# BLDC.net
KiCad netlist of a schematic drawn in Altium Designer
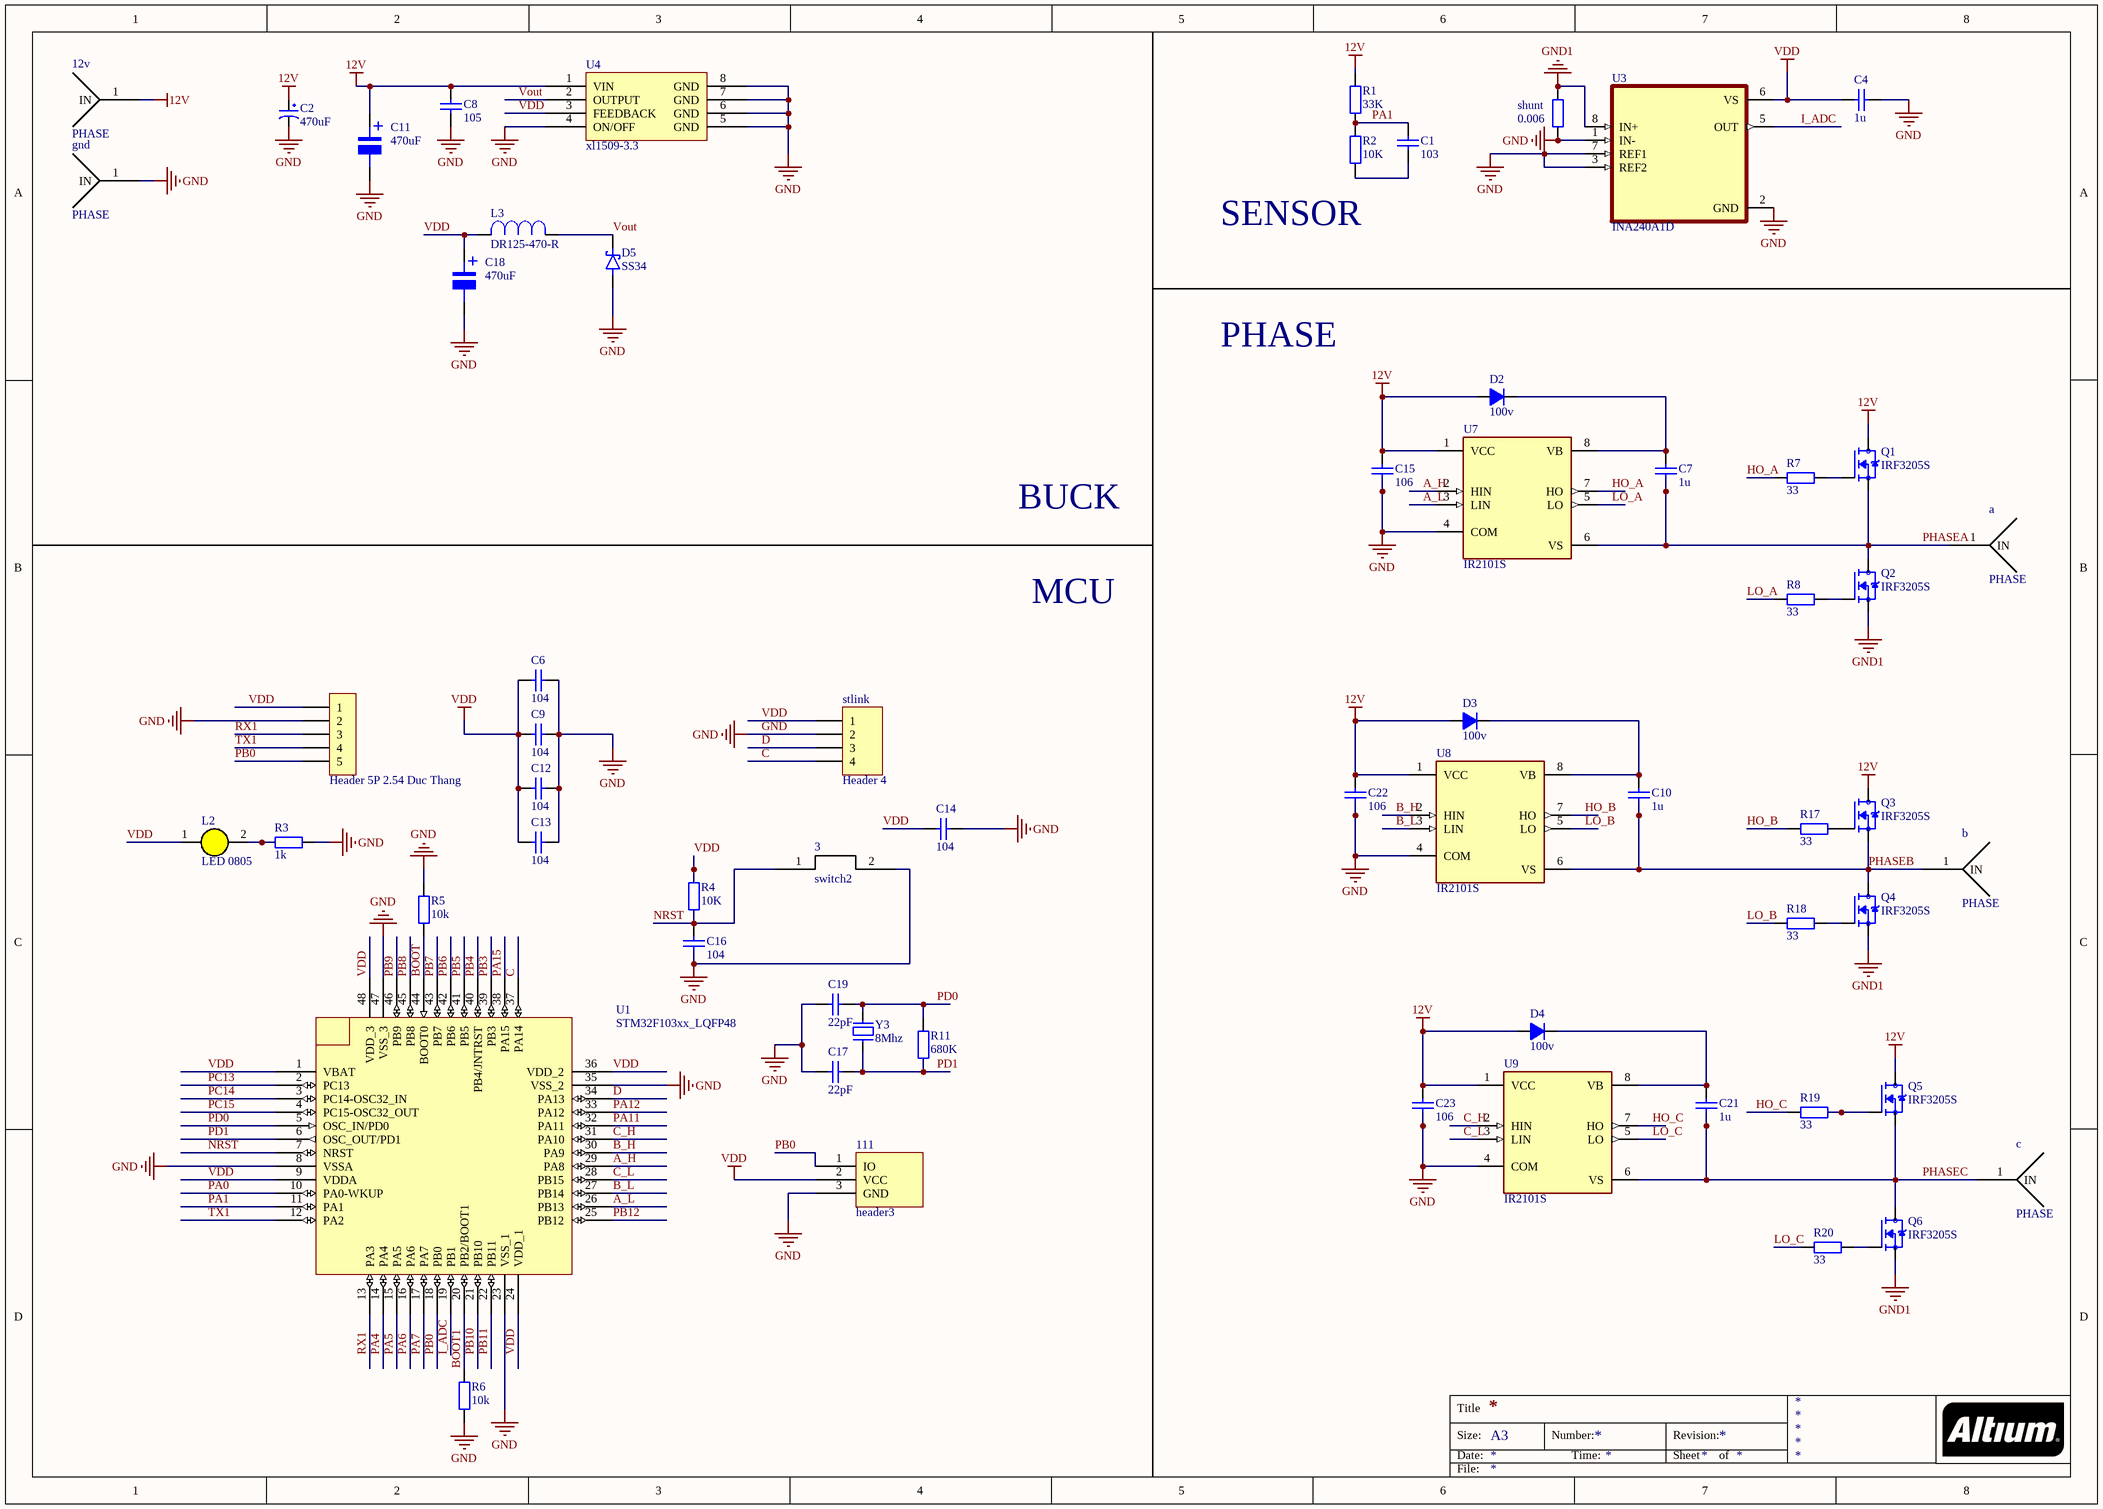
[diagram p0: BLDC.SchDoc]

(export (version "E")
  (design (tool "Eeschema 10.0.6"))
  (components
    (comp (ref "3") (value "switch2") (footprint "switch") (libsource (lib "TV1") (part "switch2")))
    (comp (ref "12v")
      (value "PHASE")
      (footprint "PCBComponent_1 - duplicate")
      (libsource (lib "TV1") (part "PHASE"))
    )
    (comp (ref "111") (value "header3") (footprint "Edge Connector") (libsource (lib "TV") (part "header3")))
    (comp (ref "a")
      (value "PHASE")
      (footprint "PCBComponent_1 - duplicate")
      (libsource (lib "TV1") (part "PHASE"))
    )
    (comp (ref "b")
      (value "PHASE")
      (footprint "PCBComponent_1 - duplicate")
      (libsource (lib "TV1") (part "PHASE"))
    )
    (comp (ref "c")
      (value "PHASE")
      (footprint "PCBComponent_1 - duplicate")
      (libsource (lib "TV1") (part "PHASE"))
    )
    (comp (ref "C1")
      (value "103")
      (footprint "tu 0805")
      (description "Dán")
      (libsource (lib "Altium_Lib_by_KhueNguyenCreator") (part "Tu 0805 22nF 50V 20%"))
    )
    (comp (ref "C2")
      (value "470uF")
      (footprint "TV1:TU HOA 10mm")
      (description "Cắm")
      (libsource (lib "TV1") (part "Tu Hoa 470uF 6.3V 8x11"))
    )
    (comp (ref "C4")
      (value "1u")
      (footprint "tu 0805")
      (description "Dán")
      (libsource (lib "Altium_Lib_by_KhueNguyenCreator") (part "Tu 0805 106 16V 10%"))
    )
    (comp (ref "C6")
      (value "104")
      (footprint "tu 0805")
      (description "Dán")
      (libsource (lib "Altium_Lib_by_KhueNguyenCreator") (part "Tu 0805 106 16V 10%"))
    )
    (comp (ref "C7")
      (value "1u")
      (footprint "tu 0805")
      (description "Dán")
      (libsource (lib "Altium_Lib_by_KhueNguyenCreator") (part "Tu 0805 10pF 50V 10%"))
    )
    (comp (ref "C8")
      (value "105")
      (footprint "tu 0805")
      (description "Dán")
      (libsource (lib "Altium_Lib_by_KhueNguyenCreator") (part "Tu 0805 105 50V 10%"))
    )
    (comp (ref "C9")
      (value "104")
      (footprint "tu 0805")
      (description "Dán")
      (libsource (lib "Altium_Lib_by_KhueNguyenCreator") (part "Tu 0805 106 16V 10%"))
    )
    (comp (ref "C10")
      (value "1u")
      (footprint "tu 0805")
      (description "Dán")
      (libsource (lib "Altium_Lib_by_KhueNguyenCreator") (part "Tu 0805 10pF 50V 10%"))
    )
    (comp (ref "C11")
      (value "470uF")
      (footprint "tu nhom 8 (f)")
      (description "Dán")
      (libsource (lib "Altium_Lib_by_KhueNguyenCreator") (part "Tu Nhom 470uF 16V"))
    )
    (comp (ref "C12")
      (value "104")
      (footprint "tu 0805")
      (description "Dán")
      (libsource (lib "Altium_Lib_by_KhueNguyenCreator") (part "Tu 0805 106 16V 10%"))
    )
    (comp (ref "C13")
      (value "104")
      (footprint "tu 0805")
      (description "Dán")
      (libsource (lib "Altium_Lib_by_KhueNguyenCreator") (part "Tu 0805 106 16V 10%"))
    )
    (comp (ref "C14")
      (value "104")
      (footprint "tu 0805")
      (description "Dán")
      (libsource (lib "Altium_Lib_by_KhueNguyenCreator") (part "Tu 0805 106 16V 10%"))
    )
    (comp (ref "C15")
      (value "106")
      (footprint "tu 0805")
      (description "Dán")
      (libsource (lib "Altium_Lib_by_KhueNguyenCreator") (part "Tu 0805 106 16V 10%"))
    )
    (comp (ref "C16")
      (value "104")
      (footprint "tu 0805")
      (description "Dán")
      (libsource (lib "Altium_Lib_by_KhueNguyenCreator") (part "Tu 0805 106 16V 10%"))
    )
    (comp (ref "C17")
      (value "22pF")
      (footprint "tu 0805")
      (description "Dán")
      (libsource (lib "Altium_Lib_by_KhueNguyenCreator") (part "Tu 0805 106 16V 10%"))
    )
    (comp (ref "C18")
      (value "470uF")
      (footprint "tu nhom 8 (f)")
      (description "Dán")
      (libsource (lib "Altium_Lib_by_KhueNguyenCreator") (part "Tu Nhom 470uF 16V"))
    )
    (comp (ref "C19")
      (value "22pF")
      (footprint "tu 0805")
      (description "Dán")
      (libsource (lib "Altium_Lib_by_KhueNguyenCreator") (part "Tu 0805 22pF 50V 10%"))
    )
    (comp (ref "C21")
      (value "1u")
      (footprint "tu 0805")
      (description "Dán")
      (libsource (lib "Altium_Lib_by_KhueNguyenCreator") (part "Tu 0805 10pF 50V 10%"))
    )
    (comp (ref "C22")
      (value "106")
      (footprint "tu 0805")
      (description "Dán")
      (libsource (lib "Altium_Lib_by_KhueNguyenCreator") (part "Tu 0805 106 16V 10%"))
    )
    (comp (ref "C23")
      (value "106")
      (footprint "tu 0805")
      (description "Dán")
      (libsource (lib "Altium_Lib_by_KhueNguyenCreator") (part "Tu 0805 106 16V 10%"))
    )
    (comp (ref "D2")
      (value "100v")
      (footprint "DIODE 0.5A")
      (description "Cắm")
      (libsource (lib "Altium_Lib_by_KhueNguyenCreator") (part "Diode 1N4148"))
    )
    (comp (ref "D3")
      (value "100v")
      (footprint "DIODE 0.5A")
      (description "Cắm")
      (libsource (lib "Altium_Lib_by_KhueNguyenCreator") (part "Diode 1N4148"))
    )
    (comp (ref "D4")
      (value "100v")
      (footprint "DIODE 0.5A")
      (description "Cắm")
      (libsource (lib "Altium_Lib_by_KhueNguyenCreator") (part "Diode 1N4148"))
    )
    (comp (ref "D5")
      (value "SS34")
      (footprint "DIOM794X590X250")
      (description "Diode Schottky 20V 3A 2Pin SMC ¦ Diodes Inc B320-13-F")
      (fields (field (name "MF") "Diodes Inc.") (field (name "MP") "B320-13-F"))
      (libsource (lib "NgTuanALib") (part "B320-13-F"))
    )
    (comp (ref "gnd")
      (value "PHASE")
      (footprint "PCBComponent_1 - duplicate")
      (libsource (lib "TV1") (part "PHASE"))
    )
    (comp (ref "H1")
      (value "Header 5P 2.54 Duc Thang")
      (footprint "XH2.54M-5")
      (description "Cắm")
      (libsource (lib "Altium_Lib_by_KhueNguyenCreator") (part "Header 5P 2.54 Duc Thang"))
    )
    (comp (ref "L2")
      (value "LED 0805")
      (footprint "LED-0805-Yellow")
      (description "Dán")
      (libsource (lib "Altium_Lib_by_KhueNguyenCreator") (part "LED 0805 Vang"))
    )
    (comp (ref "L3")
      (value "DR125-470-R")
      (footprint "INDM125125X600N")
      (fields (field (name "MF") "Eaton"))
      (libsource (lib "TV1") (part "DR125-470-R"))
    )
    (comp (ref "Q1")
      (value "IRF3205S")
      (footprint "TRANS_IRF3205S")
      (description "N-Channel 55 V 110A (Tc) 200W (Tc) Surface Mount D2PAK")
      (fields (field (name "MF") "Infineon Technologies"))
      (libsource (lib "TV1") (part "IRF3205S"))
    )
    (comp (ref "Q2")
      (value "IRF3205S")
      (footprint "TRANS_IRF3205S")
      (description "N-Channel 55 V 110A (Tc) 200W (Tc) Surface Mount D2PAK")
      (fields (field (name "MF") "Infineon Technologies"))
      (libsource (lib "TV1") (part "IRF3205S"))
    )
    (comp (ref "Q3")
      (value "IRF3205S")
      (footprint "TRANS_IRF3205S")
      (description "N-Channel 55 V 110A (Tc) 200W (Tc) Surface Mount D2PAK")
      (fields (field (name "MF") "Infineon Technologies"))
      (libsource (lib "TV1") (part "IRF3205S"))
    )
    (comp (ref "Q4")
      (value "IRF3205S")
      (footprint "TRANS_IRF3205S")
      (description "N-Channel 55 V 110A (Tc) 200W (Tc) Surface Mount D2PAK")
      (fields (field (name "MF") "Infineon Technologies"))
      (libsource (lib "TV1") (part "IRF3205S"))
    )
    (comp (ref "Q5")
      (value "IRF3205S")
      (footprint "TRANS_IRF3205S")
      (description "N-Channel 55 V 110A (Tc) 200W (Tc) Surface Mount D2PAK")
      (fields (field (name "MF") "Infineon Technologies"))
      (libsource (lib "TV1") (part "IRF3205S"))
    )
    (comp (ref "Q6")
      (value "IRF3205S")
      (footprint "TRANS_IRF3205S")
      (description "N-Channel 55 V 110A (Tc) 200W (Tc) Surface Mount D2PAK")
      (fields (field (name "MF") "Infineon Technologies"))
      (libsource (lib "TV1") (part "IRF3205S"))
    )
    (comp (ref "R1")
      (value "33K")
      (footprint "tro smd 0805")
      (description "Dán")
      (libsource (lib "Altium_Lib_by_KhueNguyenCreator") (part "Tro 0805 5% 1M"))
    )
    (comp (ref "R2")
      (value "10K")
      (footprint "tro smd 0805")
      (description "Dán")
      (libsource (lib "Altium_Lib_by_KhueNguyenCreator") (part "Tro 0805 5% 1M"))
    )
    (comp (ref "R3")
      (value "1k")
      (footprint "tro smd 0805")
      (description "Dán")
      (libsource (lib "Altium_Lib_by_KhueNguyenCreator") (part "Tro 0805 5% 1M"))
    )
    (comp (ref "R4")
      (value "10K")
      (footprint "tro smd 0805")
      (description "Dán")
      (libsource (lib "Altium_Lib_by_KhueNguyenCreator") (part "Tro 0805 5% 1M"))
    )
    (comp (ref "R5")
      (value "10k")
      (footprint "tro smd 0805")
      (description "Dán")
      (libsource (lib "Altium_Lib_by_KhueNguyenCreator") (part "Tro 0805 1% 0.22R"))
    )
    (comp (ref "R6")
      (value "10k")
      (footprint "tro smd 0805")
      (description "Dán")
      (libsource (lib "Altium_Lib_by_KhueNguyenCreator") (part "Tro 0805 1% 0.22R"))
    )
    (comp (ref "R7")
      (value "33")
      (footprint "tro smd 0805")
      (description "Dán")
      (libsource (lib "Altium_Lib_by_KhueNguyenCreator") (part "Tro 0805 1% 0.22R"))
    )
    (comp (ref "R8")
      (value "33")
      (footprint "tro smd 0805")
      (description "Dán")
      (libsource (lib "Altium_Lib_by_KhueNguyenCreator") (part "Tro 0805 1% 0.22R"))
    )
    (comp (ref "R11")
      (value "680K")
      (footprint "tro smd 0805")
      (description "Dán")
      (libsource (lib "Altium_Lib_by_KhueNguyenCreator") (part "Tro 0805 5% 1M"))
    )
    (comp (ref "R17")
      (value "33")
      (footprint "tro smd 0805")
      (description "Dán")
      (libsource (lib "Altium_Lib_by_KhueNguyenCreator") (part "Tro 0805 1% 0.22R"))
    )
    (comp (ref "R18")
      (value "33")
      (footprint "tro smd 0805")
      (description "Dán")
      (libsource (lib "Altium_Lib_by_KhueNguyenCreator") (part "Tro 0805 1% 0.22R"))
    )
    (comp (ref "R19")
      (value "33")
      (footprint "tro smd 0805")
      (description "Dán")
      (libsource (lib "Altium_Lib_by_KhueNguyenCreator") (part "Tro 0805 1% 0.22R"))
    )
    (comp (ref "R20")
      (value "33")
      (footprint "tro smd 0805")
      (description "Dán")
      (libsource (lib "Altium_Lib_by_KhueNguyenCreator") (part "Tro 0805 1% 0.22R"))
    )
    (comp (ref "shunt")
      (value "0.006")
      (footprint "PCBComponent_1")
      (description "cam")
      (libsource (lib "TV1") (part "tro shunt"))
    )
    (comp (ref "stlink")
      (value "Header 4")
      (footprint "HDR1X4")
      (description "Header, 4-Pin")
      (fields (field (name "PUBLISHER") "Altium Limited"))
      (libsource (lib "Miscellaneous Connectors") (part "Header 4"))
    )
    (comp (ref "U1")
      (value "STM32F103xx_LQFP48")
      (footprint "STM32_LQPF48")
      (fields (field (name "PUBLISHER") "Altium Limited"))
      (libsource (lib "Altium_Lib_by_KhueNguyenCreator") (part "STM32F103xx_LQFP48"))
    )
    (comp (ref "U3")
      (value "INA240A1D")
      (footprint "SOIC127P599X175-8N")
      (description "-4 to 80V, bidirectional, ultra-precise current sense amplifier with enhanced PWM rejection")
      (fields (field (name "MF") "Texas Instruments"))
      (libsource (lib "TV1") (part "INA240A1D"))
    )
    (comp (ref "U4") (value "xl1509-3.3") (footprint "BUCK-3.3") (libsource (lib "TV1") (part "xl1509-3.3")))
    (comp (ref "U7")
      (value "IR2101S")
      (footprint "SOIC127P600X175-8N")
      (description "Half-Bridge Gate Driver IC Non-Inverting 8-SOIC")
      (fields (field (name "MF") "Infineon Technologies"))
      (libsource (lib "TV1") (part "IR2101S"))
    )
    (comp (ref "U8")
      (value "IR2101S")
      (footprint "SOIC127P600X175-8N")
      (description "Half-Bridge Gate Driver IC Non-Inverting 8-SOIC")
      (fields (field (name "MF") "Infineon Technologies"))
      (libsource (lib "TV1") (part "IR2101S"))
    )
    (comp (ref "U9")
      (value "IR2101S")
      (footprint "SOIC127P600X175-8N")
      (description "Half-Bridge Gate Driver IC Non-Inverting 8-SOIC")
      (fields (field (name "MF") "Infineon Technologies"))
      (libsource (lib "TV1") (part "IR2101S"))
    )
    (comp (ref "Y3")
      (value "8Mhz")
      (footprint "Thach Anh 2 chan SMD5032")
      (description "Crystal For all Crystal 2pin.")
      (libsource (lib "Altium_Lib_by_KhueNguyenCreator") (part "Thach Anh 2 chan SMD 5032"))
    )
  )
  (nets
    (net (code "1") (name "/A_H") (class "Default")
      (node (ref "U1") (pin "29") (pinfunction "PA8_29") (pintype "bidirectional"))
      (node (ref "U7") (pin "2") (pinfunction "HIN_2") (pintype "input"))
    )
    (net (code "2") (name "/A_L") (class "Default")
      (node (ref "U1") (pin "26") (pinfunction "PB13_26") (pintype "bidirectional"))
      (node (ref "U7") (pin "3") (pinfunction "LIN_3") (pintype "input"))
    )
    (net (code "3") (name "/BOOT") (class "Default")
      (node (ref "R5") (pin "1") (pinfunction "1_1") (pintype "passive"))
      (node (ref "U1") (pin "44") (pinfunction "BOOT0_44") (pintype "input"))
    )
    (net (code "4") (name "/BOOT1") (class "Default")
      (node (ref "R6") (pin "2") (pinfunction "2_2") (pintype "passive"))
      (node (ref "U1") (pin "20") (pinfunction "PB2/BOOT1_20") (pintype "bidirectional"))
    )
    (net (code "5") (name "/B_H") (class "Default")
      (node (ref "U1") (pin "30") (pinfunction "PA9_30") (pintype "bidirectional"))
      (node (ref "U8") (pin "2") (pinfunction "HIN_2") (pintype "input"))
    )
    (net (code "6") (name "/B_L") (class "Default")
      (node (ref "U1") (pin "27") (pinfunction "PB14_27") (pintype "bidirectional"))
      (node (ref "U8") (pin "3") (pinfunction "LIN_3") (pintype "input"))
    )
    (net (code "7") (name "/C") (class "Default")
      (node (ref "U1") (pin "37") (pinfunction "PA14_37") (pintype "bidirectional"))
      (node (ref "stlink") (pin "4") (pinfunction "4_4") (pintype "passive"))
    )
    (net (code "8") (name "/C_H") (class "Default")
      (node (ref "U1") (pin "31") (pinfunction "PA10_31") (pintype "bidirectional"))
      (node (ref "U9") (pin "2") (pinfunction "HIN_2") (pintype "input"))
    )
    (net (code "9") (name "/C_L") (class "Default")
      (node (ref "U1") (pin "28") (pinfunction "PB15_28") (pintype "bidirectional"))
      (node (ref "U9") (pin "3") (pinfunction "LIN_3") (pintype "input"))
    )
    (net (code "10") (name "/D") (class "Default")
      (node (ref "U1") (pin "34") (pinfunction "PA13_34") (pintype "bidirectional"))
      (node (ref "stlink") (pin "3") (pinfunction "3_3") (pintype "passive"))
    )
    (net (code "11") (name "/HO_A") (class "Default")
      (node (ref "R7") (pin "1") (pinfunction "1_1") (pintype "passive"))
      (node (ref "U7") (pin "7") (pinfunction "HO_7") (pintype "output"))
    )
    (net (code "12") (name "/HO_B") (class "Default")
      (node (ref "R17") (pin "1") (pinfunction "1_1") (pintype "passive"))
      (node (ref "U8") (pin "7") (pinfunction "HO_7") (pintype "output"))
    )
    (net (code "13") (name "/HO_C") (class "Default")
      (node (ref "R19") (pin "1") (pinfunction "1_1") (pintype "passive"))
      (node (ref "U9") (pin "7") (pinfunction "HO_7") (pintype "output"))
    )
    (net (code "14") (name "/I_ADC") (class "Default")
      (node (ref "U1") (pin "19") (pinfunction "PB1_19") (pintype "bidirectional"))
      (node (ref "U3") (pin "5") (pinfunction "OUT_5") (pintype "output"))
    )
    (net (code "15") (name "/LO_A") (class "Default")
      (node (ref "R8") (pin "1") (pinfunction "1_1") (pintype "passive"))
      (node (ref "U7") (pin "5") (pinfunction "LO_5") (pintype "output"))
    )
    (net (code "16") (name "/LO_B") (class "Default")
      (node (ref "R18") (pin "1") (pinfunction "1_1") (pintype "passive"))
      (node (ref "U8") (pin "5") (pinfunction "LO_5") (pintype "output"))
    )
    (net (code "17") (name "/LO_C") (class "Default")
      (node (ref "R20") (pin "1") (pinfunction "1_1") (pintype "passive"))
      (node (ref "U9") (pin "5") (pinfunction "LO_5") (pintype "output"))
    )
    (net (code "18") (name "/NRST") (class "Default")
      (node (ref "3") (pin "1") (pintype "passive"))
      (node (ref "C16") (pin "2") (pinfunction "2_2") (pintype "passive"))
      (node (ref "R4") (pin "2") (pinfunction "2_2") (pintype "passive"))
      (node (ref "U1") (pin "7") (pinfunction "NRST_7") (pintype "bidirectional"))
    )
    (net (code "19") (name "/PA0") (class "Default")
      (node (ref "U1") (pin "10") (pinfunction "PA0-WKUP_10") (pintype "bidirectional"))
    )
    (net (code "20") (name "/PA1") (class "Default")
      (node (ref "C1") (pin "1") (pinfunction "1_1") (pintype "passive"))
      (node (ref "R1") (pin "2") (pinfunction "2_2") (pintype "passive"))
      (node (ref "R2") (pin "1") (pinfunction "1_1") (pintype "passive"))
      (node (ref "U1") (pin "11") (pinfunction "PA1_11") (pintype "bidirectional"))
    )
    (net (code "21") (name "/PA4") (class "Default")
      (node (ref "U1") (pin "14") (pinfunction "PA4_14") (pintype "bidirectional"))
    )
    (net (code "22") (name "/PA5") (class "Default")
      (node (ref "U1") (pin "15") (pinfunction "PA5_15") (pintype "bidirectional"))
    )
    (net (code "23") (name "/PA6") (class "Default")
      (node (ref "U1") (pin "16") (pinfunction "PA6_16") (pintype "bidirectional"))
    )
    (net (code "24") (name "/PA7") (class "Default")
      (node (ref "U1") (pin "17") (pinfunction "PA7_17") (pintype "bidirectional"))
    )
    (net (code "25") (name "/PA11") (class "Default")
      (node (ref "U1") (pin "32") (pinfunction "PA11_32") (pintype "bidirectional"))
    )
    (net (code "26") (name "/PA12") (class "Default")
      (node (ref "U1") (pin "33") (pinfunction "PA12_33") (pintype "bidirectional"))
    )
    (net (code "27") (name "/PA15") (class "Default")
      (node (ref "U1") (pin "38") (pinfunction "PA15_38") (pintype "bidirectional"))
    )
    (net (code "28") (name "/PB0") (class "Default")
      (node (ref "111") (pin "1") (pinfunction "IO_1") (pintype "passive"))
      (node (ref "H1") (pin "5") (pinfunction "5_5") (pintype "passive"))
      (node (ref "U1") (pin "18") (pinfunction "PB0_18") (pintype "bidirectional"))
    )
    (net (code "29") (name "/PB3") (class "Default")
      (node (ref "U1") (pin "39") (pinfunction "PB3_39") (pintype "bidirectional"))
    )
    (net (code "30") (name "/PB4") (class "Default")
      (node (ref "U1") (pin "40") (pinfunction "PB4/JNTRST_40") (pintype "bidirectional"))
    )
    (net (code "31") (name "/PB5") (class "Default")
      (node (ref "U1") (pin "41") (pinfunction "PB5_41") (pintype "bidirectional"))
    )
    (net (code "32") (name "/PB6") (class "Default")
      (node (ref "U1") (pin "42") (pinfunction "PB6_42") (pintype "bidirectional"))
    )
    (net (code "33") (name "/PB7") (class "Default")
      (node (ref "U1") (pin "43") (pinfunction "PB7_43") (pintype "bidirectional"))
    )
    (net (code "34") (name "/PB8") (class "Default")
      (node (ref "U1") (pin "45") (pinfunction "PB8_45") (pintype "bidirectional"))
    )
    (net (code "35") (name "/PB9") (class "Default")
      (node (ref "U1") (pin "46") (pinfunction "PB9_46") (pintype "bidirectional"))
    )
    (net (code "36") (name "/PB10") (class "Default")
      (node (ref "U1") (pin "21") (pinfunction "PB10_21") (pintype "bidirectional"))
    )
    (net (code "37") (name "/PB11") (class "Default")
      (node (ref "U1") (pin "22") (pinfunction "PB11_22") (pintype "bidirectional"))
    )
    (net (code "38") (name "/PB12") (class "Default")
      (node (ref "U1") (pin "25") (pinfunction "PB12_25") (pintype "bidirectional"))
    )
    (net (code "39") (name "/PC13") (class "Default")
      (node (ref "U1") (pin "2") (pinfunction "PC13_2") (pintype "bidirectional"))
    )
    (net (code "40") (name "/PC14") (class "Default")
      (node (ref "U1") (pin "3") (pinfunction "PC14-OSC32_IN_3") (pintype "bidirectional"))
    )
    (net (code "41") (name "/PC15") (class "Default")
      (node (ref "U1") (pin "4") (pinfunction "PC15-OSC32_OUT_4") (pintype "bidirectional"))
    )
    (net (code "42") (name "/PD0") (class "Default")
      (node (ref "C19") (pin "1") (pinfunction "1_1") (pintype "passive"))
      (node (ref "R11") (pin "2") (pinfunction "2_2") (pintype "passive"))
      (node (ref "U1") (pin "5") (pinfunction "OSC_IN/PD0_5") (pintype "input"))
      (node (ref "Y3") (pin "2") (pinfunction "2_2") (pintype "passive"))
    )
    (net (code "43") (name "/PD1") (class "Default")
      (node (ref "C17") (pin "2") (pinfunction "2_2") (pintype "passive"))
      (node (ref "R11") (pin "1") (pinfunction "1_1") (pintype "passive"))
      (node (ref "U1") (pin "6") (pinfunction "OSC_OUT/PD1_6") (pintype "output"))
      (node (ref "Y3") (pin "1") (pinfunction "1_1") (pintype "passive"))
    )
    (net (code "44") (name "/PHASEA") (class "Default")
      (node (ref "C7") (pin "2") (pinfunction "2_2") (pintype "passive"))
      (node (ref "Q1") (pin "3") (pinfunction "S_3") (pintype "passive"))
      (node (ref "Q2") (pin "2") (pinfunction "D_2") (pintype "passive"))
      (node (ref "U7") (pin "6") (pinfunction "VS_6") (pintype "power_in"))
      (node (ref "a") (pin "1") (pinfunction "IN_1") (pintype "passive"))
    )
    (net (code "45") (name "/PHASEB") (class "Default")
      (node (ref "C10") (pin "2") (pinfunction "2_2") (pintype "passive"))
      (node (ref "Q3") (pin "3") (pinfunction "S_3") (pintype "passive"))
      (node (ref "Q4") (pin "2") (pinfunction "D_2") (pintype "passive"))
      (node (ref "U8") (pin "6") (pinfunction "VS_6") (pintype "power_in"))
      (node (ref "b") (pin "1") (pinfunction "IN_1") (pintype "passive"))
    )
    (net (code "46") (name "/PHASEC") (class "Default")
      (node (ref "C21") (pin "2") (pinfunction "2_2") (pintype "passive"))
      (node (ref "Q5") (pin "3") (pinfunction "S_3") (pintype "passive"))
      (node (ref "Q6") (pin "2") (pinfunction "D_2") (pintype "passive"))
      (node (ref "U9") (pin "6") (pinfunction "VS_6") (pintype "power_in"))
      (node (ref "c") (pin "1") (pinfunction "IN_1") (pintype "passive"))
    )
    (net (code "47") (name "/RX1") (class "Default")
      (node (ref "H1") (pin "3") (pinfunction "3_3") (pintype "passive"))
      (node (ref "U1") (pin "13") (pinfunction "PA3_13") (pintype "bidirectional"))
    )
    (net (code "48") (name "/TX1") (class "Default")
      (node (ref "H1") (pin "4") (pinfunction "4_4") (pintype "passive"))
      (node (ref "U1") (pin "12") (pinfunction "PA2_12") (pintype "bidirectional"))
    )
    (net (code "49") (name "/Vout") (class "Default")
      (node (ref "D5") (pin "C") (pinfunction "C_C") (pintype "passive"))
      (node (ref "L3") (pin "1") (pinfunction "1_1") (pintype "passive"))
      (node (ref "U4") (pin "2") (pinfunction "OUTPUT_2") (pintype "passive"))
    )
    (net (code "50") (name "12V") (class "Default")
      (node (ref "12v") (pin "1") (pinfunction "IN_1") (pintype "passive"))
      (node (ref "C11") (pin "1") (pinfunction "1_1") (pintype "passive"))
      (node (ref "C15") (pin "1") (pinfunction "1_1") (pintype "passive"))
      (node (ref "C2") (pin "1") (pinfunction "1_1") (pintype "passive"))
      (node (ref "C22") (pin "1") (pinfunction "1_1") (pintype "passive"))
      (node (ref "C23") (pin "1") (pinfunction "1_1") (pintype "passive"))
      (node (ref "C8") (pin "1") (pinfunction "1_1") (pintype "passive"))
      (node (ref "D2") (pin "1") (pinfunction "A_1") (pintype "passive"))
      (node (ref "D3") (pin "1") (pinfunction "A_1") (pintype "passive"))
      (node (ref "D4") (pin "1") (pinfunction "A_1") (pintype "passive"))
      (node (ref "Q1") (pin "2") (pinfunction "D_2") (pintype "passive"))
      (node (ref "Q3") (pin "2") (pinfunction "D_2") (pintype "passive"))
      (node (ref "Q5") (pin "2") (pinfunction "D_2") (pintype "passive"))
      (node (ref "R1") (pin "1") (pinfunction "1_1") (pintype "passive"))
      (node (ref "U4") (pin "1") (pinfunction "VIN_1") (pintype "passive"))
      (node (ref "U7") (pin "1") (pinfunction "VCC_1") (pintype "power_in"))
      (node (ref "U8") (pin "1") (pinfunction "VCC_1") (pintype "power_in"))
      (node (ref "U9") (pin "1") (pinfunction "VCC_1") (pintype "power_in"))
    )
    (net (code "51") (name "GND") (class "Default")
      (node (ref "111") (pin "3") (pinfunction "GND_3") (pintype "passive"))
      (node (ref "3") (pin "2") (pintype "passive"))
      (node (ref "C11") (pin "2") (pinfunction "2_2") (pintype "passive"))
      (node (ref "C12") (pin "2") (pinfunction "2_2") (pintype "passive"))
      (node (ref "C13") (pin "2") (pinfunction "2_2") (pintype "passive"))
      (node (ref "C14") (pin "2") (pinfunction "2_2") (pintype "passive"))
      (node (ref "C15") (pin "2") (pinfunction "2_2") (pintype "passive"))
      (node (ref "C16") (pin "1") (pinfunction "1_1") (pintype "passive"))
      (node (ref "C17") (pin "1") (pinfunction "1_1") (pintype "passive"))
      (node (ref "C18") (pin "2") (pinfunction "2_2") (pintype "passive"))
      (node (ref "C19") (pin "2") (pinfunction "2_2") (pintype "passive"))
      (node (ref "C2") (pin "2") (pinfunction "2_2") (pintype "passive"))
      (node (ref "C22") (pin "2") (pinfunction "2_2") (pintype "passive"))
      (node (ref "C23") (pin "2") (pinfunction "2_2") (pintype "passive"))
      (node (ref "C4") (pin "2") (pinfunction "2_2") (pintype "passive"))
      (node (ref "C6") (pin "2") (pinfunction "2_2") (pintype "passive"))
      (node (ref "C8") (pin "2") (pinfunction "2_2") (pintype "passive"))
      (node (ref "C9") (pin "2") (pinfunction "2_2") (pintype "passive"))
      (node (ref "D5") (pin "A") (pinfunction "A_A") (pintype "passive"))
      (node (ref "H1") (pin "2") (pinfunction "2_2") (pintype "passive"))
      (node (ref "R3") (pin "2") (pinfunction "2_2") (pintype "passive"))
      (node (ref "R5") (pin "2") (pinfunction "2_2") (pintype "passive"))
      (node (ref "R6") (pin "1") (pinfunction "1_1") (pintype "passive"))
      (node (ref "U1") (pin "23") (pinfunction "VSS_1_23") (pintype "power_in"))
      (node (ref "U1") (pin "35") (pinfunction "VSS_2_35") (pintype "power_in"))
      (node (ref "U1") (pin "47") (pinfunction "VSS_3_47") (pintype "power_in"))
      (node (ref "U1") (pin "8") (pinfunction "VSSA_8") (pintype "power_in"))
      (node (ref "U3") (pin "1") (pinfunction "IN-_1") (pintype "input"))
      (node (ref "U3") (pin "2") (pinfunction "GND_2") (pintype "power_in"))
      (node (ref "U3") (pin "3") (pinfunction "REF2_3") (pintype "input"))
      (node (ref "U3") (pin "7") (pinfunction "REF1_7") (pintype "input"))
      (node (ref "U4") (pin "4") (pinfunction "ON/OFF_4") (pintype "passive"))
      (node (ref "U4") (pin "5") (pinfunction "GND_5") (pintype "passive"))
      (node (ref "U4") (pin "6") (pinfunction "GND_6") (pintype "passive"))
      (node (ref "U4") (pin "7") (pinfunction "GND_7") (pintype "passive"))
      (node (ref "U4") (pin "8") (pinfunction "GND_8") (pintype "passive"))
      (node (ref "U7") (pin "4") (pinfunction "COM_4") (pintype "power_in"))
      (node (ref "U8") (pin "4") (pinfunction "COM_4") (pintype "power_in"))
      (node (ref "U9") (pin "4") (pinfunction "COM_4") (pintype "power_in"))
      (node (ref "gnd") (pin "1") (pinfunction "IN_1") (pintype "passive"))
      (node (ref "shunt") (pin "1") (pinfunction "1_1") (pintype "passive"))
      (node (ref "stlink") (pin "2") (pinfunction "2_2") (pintype "passive"))
    )
    (net (code "52") (name "GND1") (class "Default")
      (node (ref "Q2") (pin "3") (pinfunction "S_3") (pintype "passive"))
      (node (ref "Q4") (pin "3") (pinfunction "S_3") (pintype "passive"))
      (node (ref "Q6") (pin "3") (pinfunction "S_3") (pintype "passive"))
      (node (ref "U3") (pin "8") (pinfunction "IN+_8") (pintype "input"))
      (node (ref "shunt") (pin "2") (pinfunction "2_2") (pintype "passive"))
    )
    (net (code "53") (name "Net-(C1-Pad2)") (class "Default")
      (node (ref "C1") (pin "2") (pinfunction "2_2") (pintype "passive"))
      (node (ref "R2") (pin "2") (pinfunction "2_2") (pintype "passive"))
    )
    (net (code "54") (name "Net-(D2-K)") (class "Default")
      (node (ref "C7") (pin "1") (pinfunction "1_1") (pintype "passive"))
      (node (ref "D2") (pin "2") (pinfunction "K_2") (pintype "passive"))
      (node (ref "U7") (pin "8") (pinfunction "VB_8") (pintype "power_in"))
    )
    (net (code "55") (name "Net-(D3-K)") (class "Default")
      (node (ref "C10") (pin "1") (pinfunction "1_1") (pintype "passive"))
      (node (ref "D3") (pin "2") (pinfunction "K_2") (pintype "passive"))
      (node (ref "U8") (pin "8") (pinfunction "VB_8") (pintype "power_in"))
    )
    (net (code "56") (name "Net-(D4-K)") (class "Default")
      (node (ref "C21") (pin "1") (pinfunction "1_1") (pintype "passive"))
      (node (ref "D4") (pin "2") (pinfunction "K_2") (pintype "passive"))
      (node (ref "U9") (pin "8") (pinfunction "VB_8") (pintype "power_in"))
    )
    (net (code "57") (name "Net-(L2-K)") (class "Default")
      (node (ref "L2") (pin "2") (pinfunction "K_2") (pintype "passive"))
      (node (ref "R3") (pin "1") (pinfunction "1_1") (pintype "passive"))
    )
    (net (code "58") (name "Net-(Q1-G)") (class "Default")
      (node (ref "Q1") (pin "1") (pinfunction "G_1") (pintype "passive"))
      (node (ref "R7") (pin "2") (pinfunction "2_2") (pintype "passive"))
    )
    (net (code "59") (name "Net-(Q2-G)") (class "Default")
      (node (ref "Q2") (pin "1") (pinfunction "G_1") (pintype "passive"))
      (node (ref "R8") (pin "2") (pinfunction "2_2") (pintype "passive"))
    )
    (net (code "60") (name "Net-(Q3-G)") (class "Default")
      (node (ref "Q3") (pin "1") (pinfunction "G_1") (pintype "passive"))
      (node (ref "R17") (pin "2") (pinfunction "2_2") (pintype "passive"))
    )
    (net (code "61") (name "Net-(Q4-G)") (class "Default")
      (node (ref "Q4") (pin "1") (pinfunction "G_1") (pintype "passive"))
      (node (ref "R18") (pin "2") (pinfunction "2_2") (pintype "passive"))
    )
    (net (code "62") (name "Net-(Q5-G)") (class "Default")
      (node (ref "Q5") (pin "1") (pinfunction "G_1") (pintype "passive"))
      (node (ref "R19") (pin "2") (pinfunction "2_2") (pintype "passive"))
    )
    (net (code "63") (name "Net-(Q6-G)") (class "Default")
      (node (ref "Q6") (pin "1") (pinfunction "G_1") (pintype "passive"))
      (node (ref "R20") (pin "2") (pinfunction "2_2") (pintype "passive"))
    )
    (net (code "64") (name "VDD") (class "Default")
      (node (ref "111") (pin "2") (pinfunction "VCC_2") (pintype "passive"))
      (node (ref "C12") (pin "1") (pinfunction "1_1") (pintype "passive"))
      (node (ref "C13") (pin "1") (pinfunction "1_1") (pintype "passive"))
      (node (ref "C14") (pin "1") (pinfunction "1_1") (pintype "passive"))
      (node (ref "C18") (pin "1") (pinfunction "1_1") (pintype "passive"))
      (node (ref "C4") (pin "1") (pinfunction "1_1") (pintype "passive"))
      (node (ref "C6") (pin "1") (pinfunction "1_1") (pintype "passive"))
      (node (ref "C9") (pin "1") (pinfunction "1_1") (pintype "passive"))
      (node (ref "H1") (pin "1") (pinfunction "1_1") (pintype "passive"))
      (node (ref "L2") (pin "1") (pinfunction "A_1") (pintype "passive"))
      (node (ref "L3") (pin "2") (pinfunction "2_2") (pintype "passive"))
      (node (ref "R4") (pin "1") (pinfunction "1_1") (pintype "passive"))
      (node (ref "U1") (pin "1") (pinfunction "VBAT_1") (pintype "power_in"))
      (node (ref "U1") (pin "24") (pinfunction "VDD_1_24") (pintype "power_in"))
      (node (ref "U1") (pin "36") (pinfunction "VDD_2_36") (pintype "power_in"))
      (node (ref "U1") (pin "48") (pinfunction "VDD_3_48") (pintype "power_in"))
      (node (ref "U1") (pin "9") (pinfunction "VDDA_9") (pintype "power_in"))
      (node (ref "U3") (pin "6") (pinfunction "VS_6") (pintype "power_in"))
      (node (ref "U4") (pin "3") (pinfunction "FEEDBACK_3") (pintype "passive"))
      (node (ref "stlink") (pin "1") (pinfunction "1_1") (pintype "passive"))
    )
  )
)
